# Power.net
KiCad netlist of a schematic drawn in Altium Designer
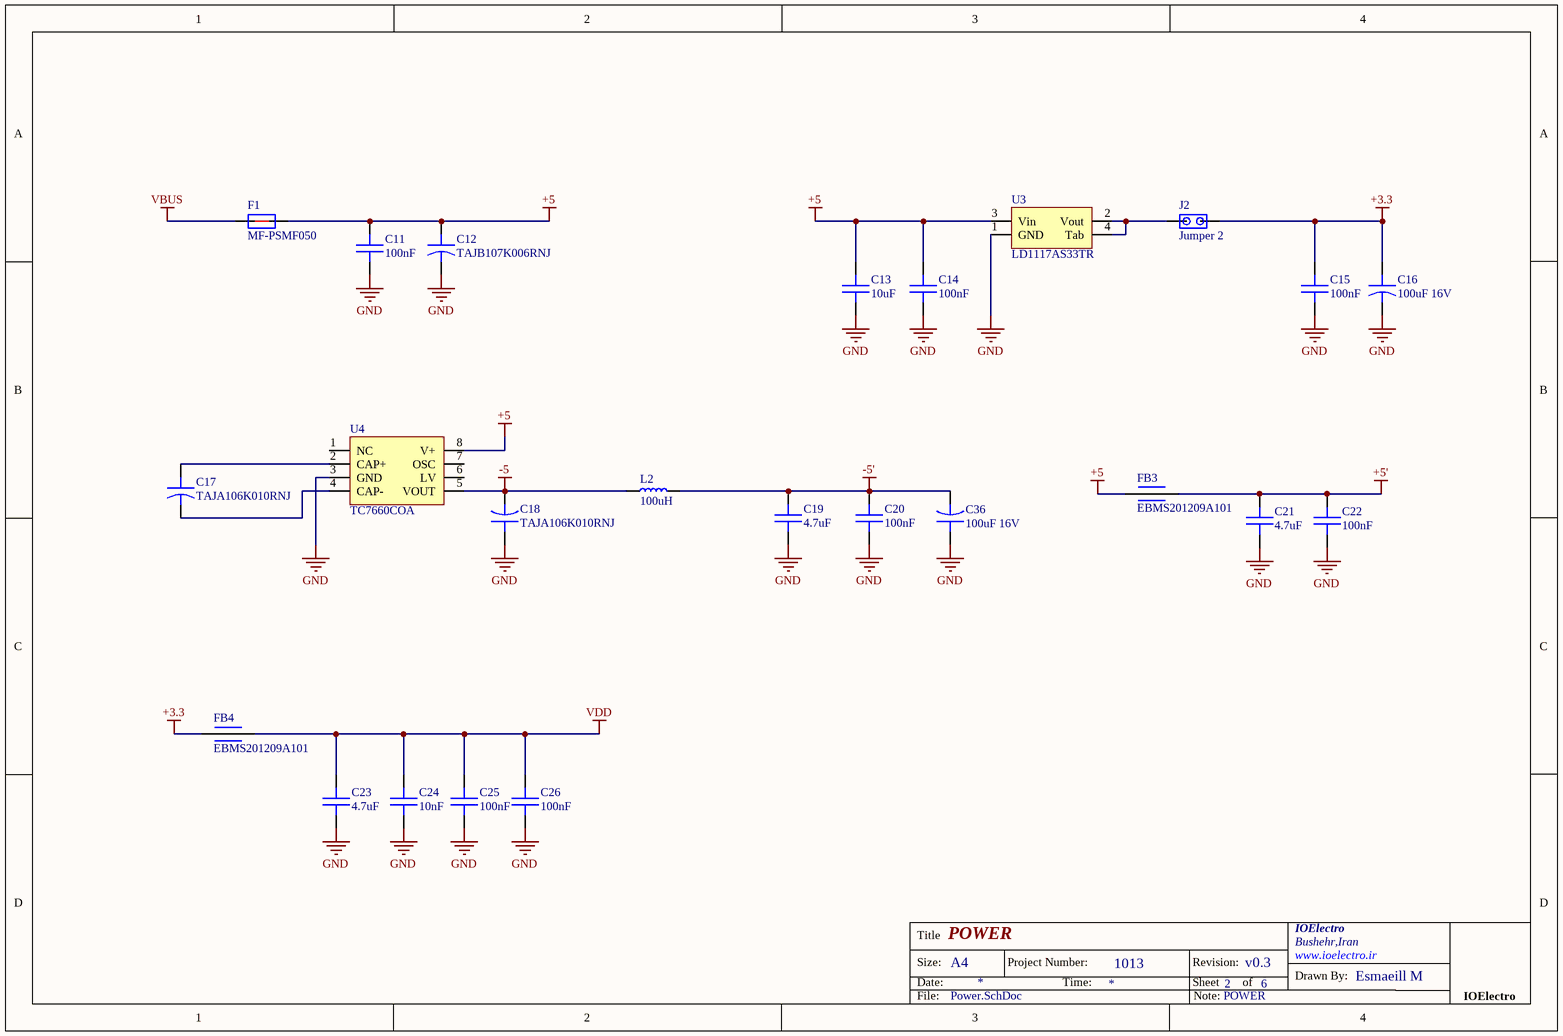
[diagram p0: Power.SchDoc]

(export (version "E")
  (design (tool "Eeschema 10.0.6"))
  (components
    (comp (ref "C11")
      (value "100nF")
      (footprint "C-0805")
      (description "SMD 0805")
      (libsource (lib "IOElectro") (part "CAP"))
    )
    (comp (ref "C12")
      (value "TAJB107K006RNJ")
      (footprint "TAJB")
      (fields
        (field (name "MANUFACTURER") "Kyocera AVX")
        (field (name "TOLERANCE") "10%")
        (field (name "VOLTAGE") "6.3V")
      )
      (libsource (lib "IOElectro") (part "TAJB107K006RNJ"))
    )
    (comp (ref "C13")
      (value "10uF")
      (footprint "C-0805")
      (description "SMD 0805")
      (libsource (lib "IOElectro") (part "CAP"))
    )
    (comp (ref "C14")
      (value "100nF")
      (footprint "C-0805")
      (description "SMD 0805")
      (libsource (lib "IOElectro") (part "CAP"))
    )
    (comp (ref "C15")
      (value "100nF")
      (footprint "C-0805")
      (description "SMD 0805")
      (libsource (lib "IOElectro") (part "CAP"))
    )
    (comp (ref "C16")
      (value "100uF 16V")
      (footprint "C-EL_6.5x7x2.5mm")
      (description "CAPACITOR ELECTROLYTIC 6.3x7mm")
      (libsource (lib "IOElectro") (part "CAP-EL"))
    )
    (comp (ref "C17")
      (value "TAJA106K010RNJ")
      (footprint "TAJA")
      (description "Capacitor;  Tantalum;  Cap 10 uF;  Tol 10%;  Vol-Rtg 10 VDC;  SMT;  3216;  ESR 3 Ohms;  TR")
      (fields (field (name "MANUFACTURER") "Kyocera AVX") (field (name "TOLERANCE") "10%"))
      (libsource (lib "IOElectro") (part "TAJA106K010RNJ"))
    )
    (comp (ref "C18")
      (value "TAJA106K010RNJ")
      (footprint "TAJA")
      (description "Capacitor;  Tantalum;  Cap 10 uF;  Tol 10%;  Vol-Rtg 10 VDC;  SMT;  3216;  ESR 3 Ohms;  TR")
      (fields (field (name "MANUFACTURER") "Kyocera AVX") (field (name "TOLERANCE") "10%"))
      (libsource (lib "IOElectro") (part "TAJA106K010RNJ"))
    )
    (comp (ref "C19")
      (value "4.7uF")
      (footprint "C-0805")
      (description "SMD 0805")
      (libsource (lib "IOElectro") (part "CAP"))
    )
    (comp (ref "C20")
      (value "100nF")
      (footprint "C-BP-Ceramic-DIP")
      (description "Ceramic Disk Capacitor 50V")
      (libsource (lib "IOElectro") (part "CAP"))
    )
    (comp (ref "C21")
      (value "4.7uF")
      (footprint "C-0805")
      (description "SMD 0805")
      (libsource (lib "IOElectro") (part "CAP"))
    )
    (comp (ref "C22")
      (value "100nF")
      (footprint "C-BP-Ceramic-DIP")
      (description "Ceramic Disk Capacitor 50V")
      (libsource (lib "IOElectro") (part "CAP"))
    )
    (comp (ref "C23")
      (value "4.7uF")
      (footprint "C-0805")
      (description "SMD 0805")
      (libsource (lib "IOElectro") (part "CAP"))
    )
    (comp (ref "C24")
      (value "10nF")
      (footprint "C-0805")
      (description "SMD 0805")
      (libsource (lib "IOElectro") (part "CAP"))
    )
    (comp (ref "C25")
      (value "100nF")
      (footprint "C-0805")
      (description "SMD 0805")
      (libsource (lib "IOElectro") (part "CAP"))
    )
    (comp (ref "C26")
      (value "100nF")
      (footprint "C-0805")
      (description "SMD 0805")
      (libsource (lib "IOElectro") (part "CAP"))
    )
    (comp (ref "C36")
      (value "100uF 16V")
      (footprint "C-EL_6.5x7x2.5mm")
      (description "CAPACITOR ELECTROLYTIC 6.3x7mm")
      (libsource (lib "IOElectro") (part "CAP-EL"))
    )
    (comp (ref "F1")
      (value "MF-PSMF050")
      (footprint "MF-PSMF")
      (description "BOURNS   MF-PSMF050X-2   FUSE, RESETTABLE PTC, 6V, 500MA, 0805")
      (fields
        (field (name "MANUFACTURER") "Bourns")
        (field (name "MANUFACTURER PART NUMBER") "MF-PSMF050X-2")
      )
      (libsource (lib "IOElectro") (part "MF-PSMF050X-2"))
    )
    (comp (ref "FB3")
      (value "EBMS201209A101")
      (footprint "L-0805")
      (description "FERRITE BEAD 0805 100R 100Mhz")
      (libsource (lib "Schlib") (part "EBMS201209A101"))
    )
    (comp (ref "FB4")
      (value "EBMS201209A101")
      (footprint "L-0805")
      (description "FERRITE BEAD 0805 100R 100Mhz")
      (libsource (lib "Schlib") (part "EBMS201209A101"))
    )
    (comp (ref "J2")
      (value "Jumper 2")
      (footprint "JAMPER-2-DIP_2.56mm")
      (description "2PIN DIP JAMPER 2.56mm")
      (libsource (lib "IOElectro") (part "JUMPER-2"))
    )
    (comp (ref "L2")
      (value "100uH")
      (footprint "L-DIP_3x7mm_pin9mm")
      (description "Axial Lead Inductors(Coils)For Signal Line 100uH 165mA")
      (libsource (lib "IOElectro") (part "AL0307-101K-LF"))
    )
    (comp (ref "U3")
      (value "LD1117AS33TR")
      (footprint "SOT-223")
      (description "IC REG LINEAR 3.3V 1A SOT223")
      (fields (field (name "MANUFACTURER") "STMicroelectronics"))
      (libsource (lib "IOElectro") (part "LD1117AS33TR"))
    )
    (comp (ref "U4")
      (value "TC7660COA")
      (footprint "SOIC-8")
      (description "IC REG SWTCHD CAP INV 20MA 8SOIC")
      (fields (field (name "MANUFACTURER") "Microchip"))
      (libsource (lib "IOElectro") (part "TC7660COA"))
    )
  )
  (nets
    (net (code "1") (name "+3.3") (class "Default")
      (node (ref "C15") (pin "1") (pinfunction "1_1") (pintype "passive"))
      (node (ref "C16") (pin "A") (pinfunction "A_A") (pintype "passive"))
      (node (ref "FB4") (pin "1") (pinfunction "1_1") (pintype "passive"))
      (node (ref "J2") (pin "1") (pinfunction "1_1") (pintype "passive"))
    )
    (net (code "2") (name "+5") (class "Default")
      (node (ref "C11") (pin "1") (pinfunction "1_1") (pintype "passive"))
      (node (ref "C12") (pin "A") (pinfunction "A_A") (pintype "passive"))
      (node (ref "C13") (pin "1") (pinfunction "1_1") (pintype "passive"))
      (node (ref "C14") (pin "1") (pinfunction "1_1") (pintype "passive"))
      (node (ref "F1") (pin "2") (pinfunction "2_2") (pintype "passive"))
      (node (ref "FB3") (pin "1") (pinfunction "1_1") (pintype "passive"))
      (node (ref "U3") (pin "3") (pinfunction "Vin_3") (pintype "passive"))
      (node (ref "U4") (pin "8") (pinfunction "V+_8") (pintype "passive"))
    )
    (net (code "3") (name "+5'") (class "Default")
      (node (ref "C21") (pin "1") (pinfunction "1_1") (pintype "passive"))
      (node (ref "C22") (pin "2") (pinfunction "2_2") (pintype "passive"))
      (node (ref "FB3") (pin "2") (pinfunction "2_2") (pintype "passive"))
    )
    (net (code "4") (name "-5") (class "Default")
      (node (ref "C18") (pin "K") (pinfunction "K_K") (pintype "passive"))
      (node (ref "L2") (pin "1") (pinfunction "1_1") (pintype "passive"))
      (node (ref "U4") (pin "5") (pinfunction "VOUT_5") (pintype "passive"))
    )
    (net (code "5") (name "-5'") (class "Default")
      (node (ref "C19") (pin "1") (pinfunction "1_1") (pintype "passive"))
      (node (ref "C20") (pin "2") (pinfunction "2_2") (pintype "passive"))
      (node (ref "C36") (pin "K") (pinfunction "K_K") (pintype "passive"))
      (node (ref "L2") (pin "2") (pinfunction "2_2") (pintype "passive"))
    )
    (net (code "6") (name "GND") (class "Default")
      (node (ref "C11") (pin "2") (pinfunction "2_2") (pintype "passive"))
      (node (ref "C12") (pin "K") (pinfunction "K_K") (pintype "passive"))
      (node (ref "C13") (pin "2") (pinfunction "2_2") (pintype "passive"))
      (node (ref "C14") (pin "2") (pinfunction "2_2") (pintype "passive"))
      (node (ref "C15") (pin "2") (pinfunction "2_2") (pintype "passive"))
      (node (ref "C16") (pin "K") (pinfunction "K_K") (pintype "passive"))
      (node (ref "C18") (pin "A") (pinfunction "A_A") (pintype "passive"))
      (node (ref "C19") (pin "2") (pinfunction "2_2") (pintype "passive"))
      (node (ref "C20") (pin "1") (pinfunction "1_1") (pintype "passive"))
      (node (ref "C21") (pin "2") (pinfunction "2_2") (pintype "passive"))
      (node (ref "C22") (pin "1") (pinfunction "1_1") (pintype "passive"))
      (node (ref "C23") (pin "2") (pinfunction "2_2") (pintype "passive"))
      (node (ref "C24") (pin "2") (pinfunction "2_2") (pintype "passive"))
      (node (ref "C25") (pin "2") (pinfunction "2_2") (pintype "passive"))
      (node (ref "C26") (pin "2") (pinfunction "2_2") (pintype "passive"))
      (node (ref "C36") (pin "A") (pinfunction "A_A") (pintype "passive"))
      (node (ref "U3") (pin "1") (pinfunction "GND_1") (pintype "passive"))
      (node (ref "U4") (pin "3") (pinfunction "GND_3") (pintype "passive"))
    )
    (net (code "7") (name "Net-(U3-Tab)") (class "Default")
      (node (ref "J2") (pin "2") (pinfunction "2_2") (pintype "passive"))
      (node (ref "U3") (pin "2") (pinfunction "Vout_2") (pintype "passive"))
      (node (ref "U3") (pin "4") (pinfunction "Tab_4") (pintype "passive"))
    )
    (net (code "8") (name "Net-(U4-CAP+)") (class "Default")
      (node (ref "C17") (pin "A") (pinfunction "A_A") (pintype "passive"))
      (node (ref "U4") (pin "2") (pinfunction "CAP+_2") (pintype "passive"))
    )
    (net (code "9") (name "Net-(U4-CAP-)") (class "Default")
      (node (ref "C17") (pin "K") (pinfunction "K_K") (pintype "passive"))
      (node (ref "U4") (pin "4") (pinfunction "CAP-_4") (pintype "passive"))
    )
    (net (code "10") (name "VBUS") (class "Default")
      (node (ref "F1") (pin "1") (pinfunction "1_1") (pintype "passive"))
    )
    (net (code "11") (name "VDD") (class "Default")
      (node (ref "C23") (pin "1") (pinfunction "1_1") (pintype "passive"))
      (node (ref "C24") (pin "1") (pinfunction "1_1") (pintype "passive"))
      (node (ref "C25") (pin "1") (pinfunction "1_1") (pintype "passive"))
      (node (ref "C26") (pin "1") (pinfunction "1_1") (pintype "passive"))
      (node (ref "FB4") (pin "2") (pinfunction "2_2") (pintype "passive"))
    )
    (net (code "12") (name "unconnected-(U4-LV-Pad6)") (class "Default")
      (node (ref "U4") (pin "6") (pinfunction "LV_6") (pintype "passive"))
    )
    (net (code "13") (name "unconnected-(U4-NC-Pad1)") (class "Default")
      (node (ref "U4") (pin "1") (pinfunction "NC_1") (pintype "passive"))
    )
    (net (code "14") (name "unconnected-(U4-OSC-Pad7)") (class "Default")
      (node (ref "U4") (pin "7") (pinfunction "OSC_7") (pintype "passive"))
    )
  )
)
